# MCP4725.net
KiCad netlist of a schematic drawn in Altium Designer
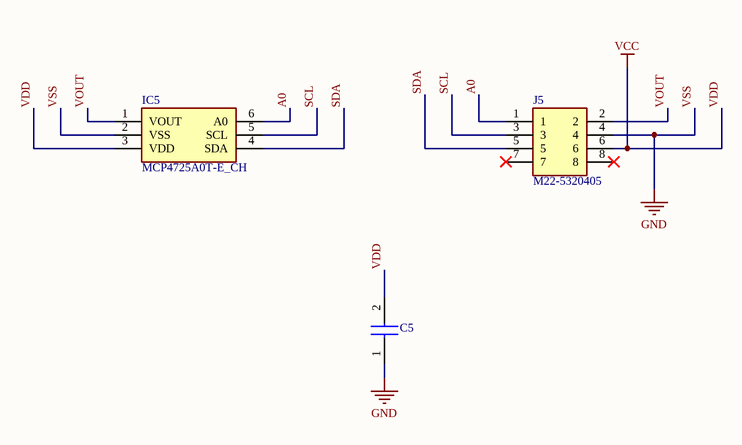
[diagram p0: MCP4725.SchDoc]

(export (version "E")
  (design (tool "Eeschema 10.0.6"))
  (components
    (comp (ref "C5")
      (value "GRM21BR71C105MA01K")
      (footprint "SamacSys:CAPC2012X145N")
      (description "Capacitor")
      (fields (field (name "MOUSER PART NUMBER") "81-GRM21R71C105MA01K"))
      (libsource (lib "*") (part "GRM21BR71C105MA01K"))
    )
    (comp (ref "IC5")
      (value "MCP4725A0T-E_CH")
      (footprint "SamacSys:SOT95P270X145-6N")
      (description "Integrated Circuit")
      (fields
        (field (name "MANUFACTURER_PART_NUMBER") "MCP4725A0T-E/CH")
        (field (name "MOUSER PART NUMBER") "579-MCP4725A0TECH")
      )
      (libsource (lib "*") (part "MCP4725A0T-E_CH"))
    )
    (comp (ref "J5")
      (value "M22-5320405")
      (footprint "SamacSys:HUSSP8W50P200_2X4_800X400X500P")
      (description "Connector")
      (fields (field (name "MOUSER PART NUMBER") "855-M22-5320405"))
      (libsource (lib "*") (part "M22-5320405"))
    )
  )
  (nets
    (net (code "1") (name "/A0") (class "Default")
      (node (ref "IC5") (pin "6") (pinfunction "A0_6") (pintype "passive"))
      (node (ref "J5") (pin "1") (pinfunction "1_1") (pintype "passive"))
    )
    (net (code "2") (name "/SCL") (class "Default")
      (node (ref "IC5") (pin "5") (pinfunction "SCL_5") (pintype "passive"))
      (node (ref "J5") (pin "3") (pinfunction "3_3") (pintype "passive"))
    )
    (net (code "3") (name "/SDA") (class "Default")
      (node (ref "IC5") (pin "4") (pinfunction "SDA_4") (pintype "passive"))
      (node (ref "J5") (pin "5") (pinfunction "5_5") (pintype "passive"))
    )
    (net (code "4") (name "/VOUT") (class "Default")
      (node (ref "IC5") (pin "1") (pinfunction "VOUT_1") (pintype "passive"))
      (node (ref "J5") (pin "2") (pinfunction "2_2") (pintype "passive"))
    )
    (net (code "5") (name "GND") (class "Default")
      (node (ref "C5") (pin "1") (pinfunction "1_1") (pintype "passive"))
      (node (ref "IC5") (pin "2") (pinfunction "VSS_2") (pintype "passive"))
      (node (ref "J5") (pin "4") (pinfunction "4_4") (pintype "passive"))
    )
    (net (code "6") (name "VCC") (class "Default")
      (node (ref "C5") (pin "2") (pinfunction "2_2") (pintype "passive"))
      (node (ref "IC5") (pin "3") (pinfunction "VDD_3") (pintype "passive"))
      (node (ref "J5") (pin "6") (pinfunction "6_6") (pintype "passive"))
    )
    (net (code "7") (name "unconnected-(J5-Pad7)") (class "Default")
      (node (ref "J5") (pin "7") (pinfunction "7_7") (pintype "passive+no_connect"))
    )
    (net (code "8") (name "unconnected-(J5-Pad8)") (class "Default")
      (node (ref "J5") (pin "8") (pinfunction "8_8") (pintype "passive+no_connect"))
    )
  )
)
